# badge4.net
KiCad netlist of a schematic drawn in Altium Designer
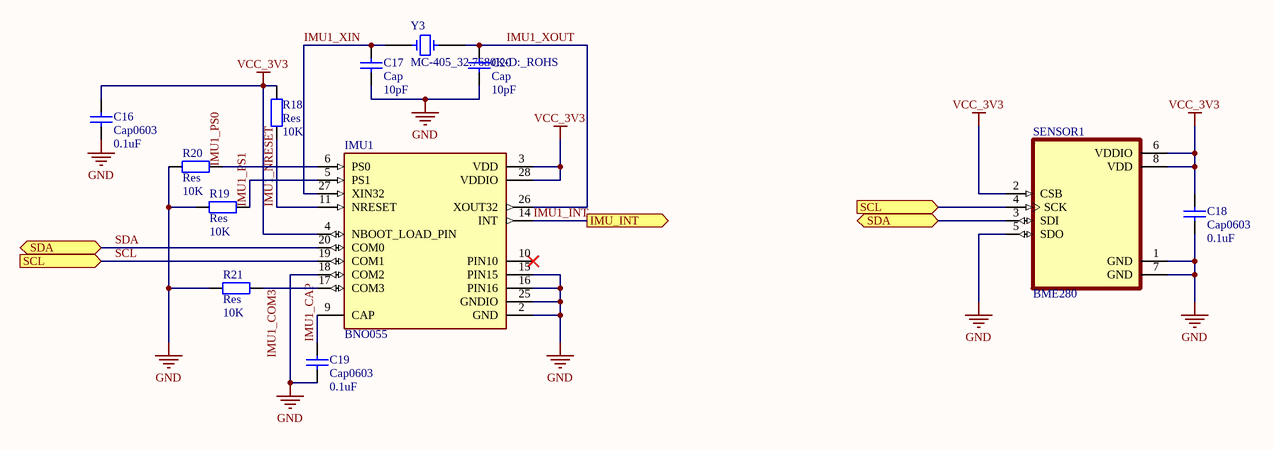
[diagram p0: badge4.SchDoc]

(export (version "E")
  (design (tool "Eeschema 10.0.6"))
  (components
    (comp (ref "C16")
      (value "Cap0603")
      (footprint "C0603")
      (description "Capacitor")
      (fields
        (field (name "ALTIUM_VALUE") "0.1uF")
        (field (name "MF") "KEMET")
        (field (name "MP") "C0603C104Z3VACTU")
        (field (name "PUBLISHER") "Altium Limited")
      )
      (libsource (lib "badge") (part "Cap0603"))
    )
    (comp (ref "C17")
      (value "Cap")
      (footprint "C0603")
      (description "Capacitor")
      (fields
        (field (name "ALTIUM_VALUE") "10pF")
        (field (name "MF") "KEMET")
        (field (name "MP") "C0603C100J1GACTU")
        (field (name "PUBLISHER") "Altium Limited")
      )
      (libsource (lib "badge") (part "Cap"))
    )
    (comp (ref "C18")
      (value "Cap0603")
      (footprint "C0603")
      (description "Capacitor")
      (fields
        (field (name "ALTIUM_VALUE") "0.1uF")
        (field (name "MF") "KEMET")
        (field (name "MP") "C0603C104Z3VACTU")
        (field (name "PUBLISHER") "Altium Limited")
      )
      (libsource (lib "badge") (part "Cap0603"))
    )
    (comp (ref "C19")
      (value "Cap0603")
      (footprint "C0603")
      (description "Capacitor")
      (fields
        (field (name "ALTIUM_VALUE") "0.1uF")
        (field (name "MF") "KEMET")
        (field (name "MP") "C0603C104Z3VACTU")
        (field (name "PUBLISHER") "Altium Limited")
      )
      (libsource (lib "badge") (part "Cap0603"))
    )
    (comp (ref "C20")
      (value "Cap")
      (footprint "C0603")
      (description "Capacitor")
      (fields
        (field (name "ALTIUM_VALUE") "10pF")
        (field (name "MF") "KEMET")
        (field (name "MP") "C0603C100J1GACTU")
        (field (name "PUBLISHER") "Altium Limited")
      )
      (libsource (lib "badge") (part "Cap"))
    )
    (comp (ref "IMU1")
      (value "BNO055")
      (footprint "LGA28R50P4X10_380X520X100")
      (description "Accelerometer, Gyroscope, Magnetometer, 9 Axis Sensor IÂ²C, UART Output")
      (fields (field (name "MF") "Bosch") (field (name "DIGI-KEY_PART_NUMBER") "828-1058-1-ND"))
      (libsource (lib "badge") (part "BNO055"))
    )
    (comp (ref "R18")
      (value "Res")
      (footprint "R0603")
      (description "Resistor")
      (fields
        (field (name "ALTIUM_VALUE") "10K")
        (field (name "MF") "Yageo")
        (field (name "MP") "RC0603JR-0710KL")
        (field (name "PUBLISHER") "Altium Limited")
      )
      (libsource (lib "") (part "Res_1"))
    )
    (comp (ref "R19")
      (value "Res")
      (footprint "R0603")
      (description "Resistor")
      (fields
        (field (name "ALTIUM_VALUE") "10K")
        (field (name "MF") "Yageo")
        (field (name "MP") "RC0603JR-0710KL")
        (field (name "PUBLISHER") "Altium Limited")
      )
      (libsource (lib "badge") (part "Res"))
    )
    (comp (ref "R20")
      (value "Res")
      (footprint "R0603")
      (description "Resistor")
      (fields
        (field (name "ALTIUM_VALUE") "10K")
        (field (name "MF") "Yageo")
        (field (name "MP") "RC0603JR-0710KL")
        (field (name "PUBLISHER") "Altium Limited")
      )
      (libsource (lib "badge") (part "Res"))
    )
    (comp (ref "R21")
      (value "Res")
      (footprint "R0603")
      (description "Resistor")
      (fields
        (field (name "ALTIUM_VALUE") "10K")
        (field (name "MF") "Yageo")
        (field (name "MP") "RC0603JR-0710KL")
        (field (name "PUBLISHER") "Altium Limited")
      )
      (libsource (lib "badge") (part "Res"))
    )
    (comp (ref "SENSOR1")
      (value "BME280")
      (footprint "PSON65P250X250X100-8N")
      (description "Humidity Temperature Sensor 0 ~ 100% RH IÂ²C, SPI Â±3% 1s Surface Mount")
      (fields (field (name "MF") "Bosch"))
      (libsource (lib "badge") (part "BME280"))
    )
    (comp (ref "Y3")
      (value "MC-405_32.7680K-D:_ROHS")
      (footprint "XTAL320X150")
      (description "32.768kHz Â±20ppm Crystal 35 kOhms 4-SOJ, 2.29mm pitch")
      (fields (field (name "MP") "DNP"))
      (libsource (lib "badge") (part "MC-405_32.7680K-D{colon}_ROHS"))
    )
  )
  (nets
    (net (code "1") (name "/IMU1_CAP") (class "Default")
      (node (ref "C19") (pin "2") (pinfunction "2_2") (pintype "passive"))
      (node (ref "IMU1") (pin "9") (pinfunction "CAP_9") (pintype "passive"))
    )
    (net (code "2") (name "/IMU1_COM3") (class "Default")
      (node (ref "IMU1") (pin "17") (pinfunction "COM3_17") (pintype "bidirectional"))
      (node (ref "R21") (pin "2") (pinfunction "2_2") (pintype "passive"))
    )
    (net (code "3") (name "/IMU1_INT") (class "Default")
      (node (ref "IMU1") (pin "14") (pinfunction "INT_14") (pintype "output"))
    )
    (net (code "4") (name "/IMU1_NRESET") (class "Default")
      (node (ref "IMU1") (pin "11") (pinfunction "NRESET_11") (pintype "input"))
      (node (ref "R18") (pin "1") (pinfunction "1_1") (pintype "passive"))
    )
    (net (code "5") (name "/IMU1_PS0") (class "Default")
      (node (ref "IMU1") (pin "6") (pinfunction "PS0_6") (pintype "input"))
      (node (ref "R20") (pin "2") (pinfunction "2_2") (pintype "passive"))
    )
    (net (code "6") (name "/IMU1_PS1") (class "Default")
      (node (ref "IMU1") (pin "5") (pinfunction "PS1_5") (pintype "input"))
      (node (ref "R19") (pin "2") (pinfunction "2_2") (pintype "passive"))
    )
    (net (code "7") (name "/IMU1_XIN") (class "Default")
      (node (ref "C17") (pin "2") (pinfunction "2_2") (pintype "passive"))
      (node (ref "IMU1") (pin "27") (pinfunction "XIN32_27") (pintype "input"))
      (node (ref "Y3") (pin "2") (pinfunction "2_2") (pintype "passive"))
    )
    (net (code "8") (name "/IMU1_XOUT") (class "Default")
      (node (ref "C20") (pin "2") (pinfunction "2_2") (pintype "passive"))
      (node (ref "IMU1") (pin "26") (pinfunction "XOUT32_26") (pintype "output"))
      (node (ref "Y3") (pin "1") (pinfunction "1_1") (pintype "passive"))
    )
    (net (code "9") (name "/SCL") (class "Default")
      (node (ref "IMU1") (pin "19") (pinfunction "COM1_19") (pintype "bidirectional"))
      (node (ref "SENSOR1") (pin "4") (pinfunction "SCK_4") (pintype "input"))
    )
    (net (code "10") (name "/SDA") (class "Default")
      (node (ref "IMU1") (pin "20") (pinfunction "COM0_20") (pintype "bidirectional"))
      (node (ref "SENSOR1") (pin "3") (pinfunction "SDI_3") (pintype "bidirectional"))
    )
    (net (code "11") (name "GND") (class "Default")
      (node (ref "C16") (pin "1") (pinfunction "1_1") (pintype "passive"))
      (node (ref "C17") (pin "1") (pinfunction "1_1") (pintype "passive"))
      (node (ref "C18") (pin "1") (pinfunction "1_1") (pintype "passive"))
      (node (ref "C19") (pin "1") (pinfunction "1_1") (pintype "passive"))
      (node (ref "C20") (pin "1") (pinfunction "1_1") (pintype "passive"))
      (node (ref "IMU1") (pin "15") (pinfunction "PIN15_15") (pintype "power_in"))
      (node (ref "IMU1") (pin "16") (pinfunction "PIN16_16") (pintype "power_in"))
      (node (ref "IMU1") (pin "18") (pinfunction "COM2_18") (pintype "bidirectional"))
      (node (ref "IMU1") (pin "2") (pinfunction "GND_2") (pintype "power_in"))
      (node (ref "IMU1") (pin "25") (pinfunction "GNDIO_25") (pintype "power_in"))
      (node (ref "R19") (pin "1") (pinfunction "1_1") (pintype "passive"))
      (node (ref "R20") (pin "1") (pinfunction "1_1") (pintype "passive"))
      (node (ref "R21") (pin "1") (pinfunction "1_1") (pintype "passive"))
      (node (ref "SENSOR1") (pin "1") (pinfunction "GND_1") (pintype "power_in"))
      (node (ref "SENSOR1") (pin "5") (pinfunction "SDO_5") (pintype "bidirectional"))
      (node (ref "SENSOR1") (pin "7") (pinfunction "GND_7") (pintype "power_in"))
    )
    (net (code "12") (name "VCC_3V3") (class "Default")
      (node (ref "C16") (pin "2") (pinfunction "2_2") (pintype "passive"))
      (node (ref "C18") (pin "2") (pinfunction "2_2") (pintype "passive"))
      (node (ref "IMU1") (pin "28") (pinfunction "VDDIO_28") (pintype "power_in"))
      (node (ref "IMU1") (pin "3") (pinfunction "VDD_3") (pintype "power_in"))
      (node (ref "IMU1") (pin "4") (pinfunction "NBOOT_LOAD_PIN_4") (pintype "bidirectional"))
      (node (ref "R18") (pin "2") (pinfunction "2_2") (pintype "passive"))
      (node (ref "SENSOR1") (pin "2") (pinfunction "CSB_2") (pintype "input"))
      (node (ref "SENSOR1") (pin "6") (pinfunction "VDDIO_6") (pintype "power_in"))
      (node (ref "SENSOR1") (pin "8") (pinfunction "VDD_8") (pintype "power_in"))
    )
    (net (code "13") (name "unconnected-(IMU1-PIN10-Pad10)") (class "Default")
      (node (ref "IMU1") (pin "10") (pinfunction "PIN10_10") (pintype "power_in+no_connect"))
    )
  )
)
